# p214_001_001.net
KiCad netlist of a schematic drawn in EAGLE
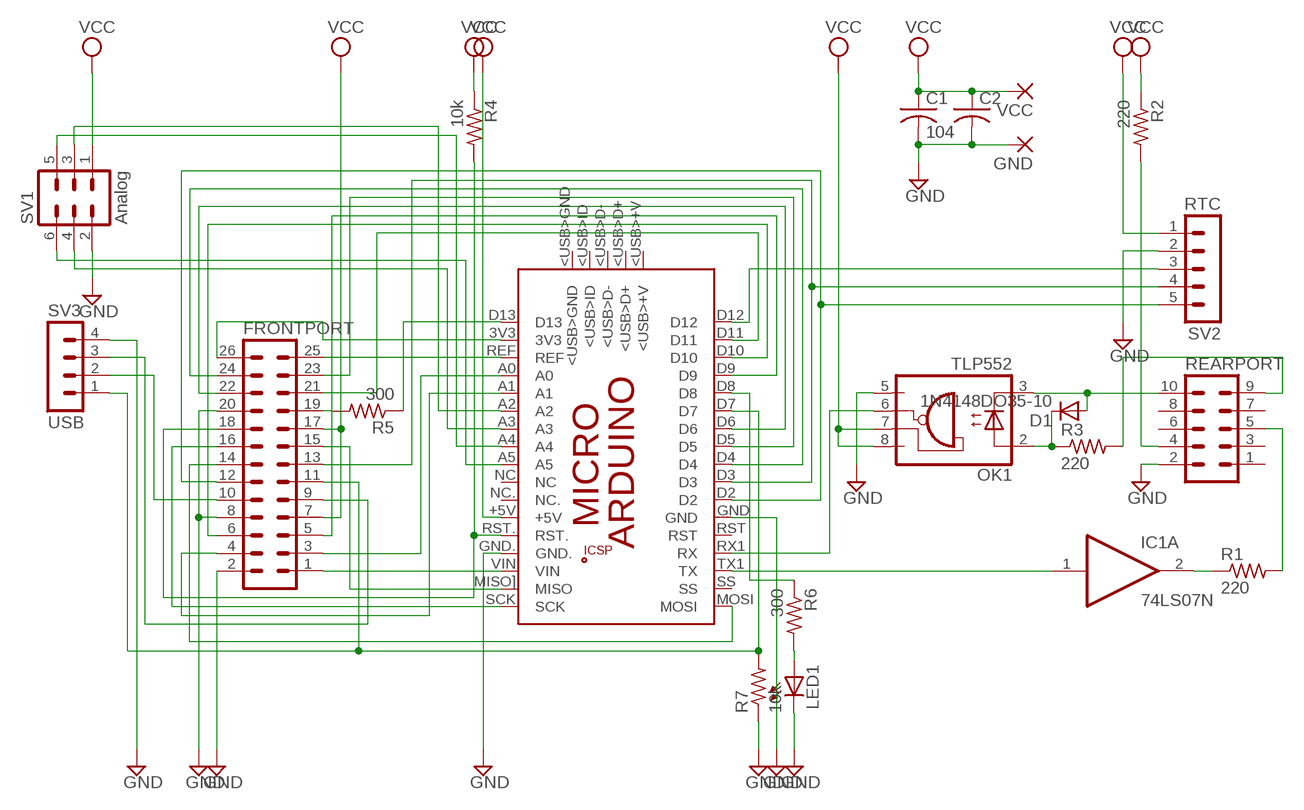
[diagram p0: schematic, sheet 1]

(export (version "E")
  (design (tool "Eeschema 10.0.6"))
  (components
    (comp (ref "C1")
      (value "104")
      (footprint "eagle-import:C025-025X050")
      (libsource (lib "eagle-import") (part "C-US025-025X050"))
    )
    (comp (ref "C2")
      (value "C-US050-075X075")
      (footprint "eagle-import:C050-075X075")
      (libsource (lib "eagle-import") (part "C-US050-075X075"))
    )
    (comp (ref "D1")
      (value "1N4148DO35-10")
      (footprint "eagle-import:DO35-10")
      (libsource (lib "eagle-import") (part "1N4148DO35-10"))
    )
    (comp (ref "FRONTPORT")
      (value "ML26L")
      (footprint "eagle-import:ML26L")
      (libsource (lib "eagle-import") (part "ML26L"))
    )
    (comp (ref "GND")
      (value "1,6/0,9")
      (footprint "eagle-import:1,6_0,9")
      (libsource (lib "eagle-import") (part "1,6/0,9"))
    )
    (comp (ref "IC1")
      (value "74LS07N")
      (footprint "eagle-import:DIL14")
      (libsource (lib "eagle-import") (part "7407NLS"))
    )
    (comp (ref "LED1")
      (value "LED3MM")
      (footprint "eagle-import:LED3MM")
      (libsource (lib "eagle-import") (part "LED3MM"))
    )
    (comp (ref "OK1")
      (value "TLP552")
      (footprint "eagle-import:DIL08")
      (fields (field (name "MPN") "6N137"))
      (libsource (lib "eagle-import") (part "6N137"))
    )
    (comp (ref "PCB1")
      (value "ARDUINO_MICRO")
      (footprint "eagle-import:ARDUINO_MICRO")
      (libsource (lib "eagle-import") (part "ARDUINO_MICRO"))
    )
    (comp (ref "R1")
      (value "220")
      (footprint "eagle-import:0204_7")
      (libsource (lib "eagle-import") (part "R-US_0204/7"))
    )
    (comp (ref "R2")
      (value "220")
      (footprint "eagle-import:0204_7")
      (libsource (lib "eagle-import") (part "R-US_0204/7"))
    )
    (comp (ref "R3")
      (value "220")
      (footprint "eagle-import:0204_7")
      (libsource (lib "eagle-import") (part "R-US_0204/7"))
    )
    (comp (ref "R4")
      (value "10k")
      (footprint "eagle-import:0204_7")
      (libsource (lib "eagle-import") (part "R-US_0204/7"))
    )
    (comp (ref "R5")
      (value "300")
      (footprint "eagle-import:0204_7")
      (libsource (lib "eagle-import") (part "R-US_0204/7"))
    )
    (comp (ref "R6")
      (value "300")
      (footprint "eagle-import:0204_7")
      (libsource (lib "eagle-import") (part "R-US_0204/7"))
    )
    (comp (ref "R7")
      (value "10k")
      (footprint "eagle-import:0204_7")
      (libsource (lib "eagle-import") (part "R-US_0204/7"))
    )
    (comp (ref "REARPORT")
      (value "ML10L")
      (footprint "eagle-import:ML10L")
      (libsource (lib "eagle-import") (part "ML10L"))
    )
    (comp (ref "SV1")
      (value "Analog")
      (footprint "eagle-import:MA03-2")
      (libsource (lib "eagle-import") (part "MA03-2"))
    )
    (comp (ref "SV2")
      (value "RTC")
      (footprint "eagle-import:MA05-1")
      (libsource (lib "eagle-import") (part "MA05-1"))
    )
    (comp (ref "SV3")
      (value "USB")
      (footprint "eagle-import:MA04-1")
      (libsource (lib "eagle-import") (part "MA04-1"))
    )
    (comp (ref "VCC")
      (value "1,6/0,9")
      (footprint "eagle-import:1,6_0,9")
      (libsource (lib "eagle-import") (part "1,6/0,9"))
    )
  )
  (nets
    (net (code "1") (name "GND") (class "Default")
      (node (ref "C1") (pin "2") (pinfunction "2_2") (pintype "passive"))
      (node (ref "C2") (pin "2") (pinfunction "2_2") (pintype "passive"))
      (node (ref "FRONTPORT") (pin "2") (pinfunction "2_2") (pintype "passive"))
      (node (ref "FRONTPORT") (pin "20") (pinfunction "20_20") (pintype "passive"))
      (node (ref "FRONTPORT") (pin "8") (pinfunction "8_8") (pintype "passive"))
      (node (ref "GND") (pin "1") (pinfunction "P_1") (pintype "passive"))
      (node (ref "LED1") (pin "K") (pinfunction "C_K") (pintype "passive"))
      (node (ref "OK1") (pin "5") (pinfunction "GND_5") (pintype "passive"))
      (node (ref "PCB1") (pin "GND") (pinfunction "GND_GND") (pintype "bidirectional"))
      (node (ref "PCB1") (pin "GND.") (pinfunction "GND._GND.") (pintype "bidirectional"))
      (node (ref "R7") (pin "1") (pinfunction "1_1") (pintype "passive"))
      (node (ref "REARPORT") (pin "2") (pinfunction "2_2") (pintype "passive"))
      (node (ref "SV1") (pin "2") (pinfunction "2_2") (pintype "passive"))
      (node (ref "SV2") (pin "2") (pinfunction "2_2") (pintype "passive"))
      (node (ref "SV3") (pin "4") (pinfunction "4_4") (pintype "passive"))
    )
    (net (code "2") (name "Net-(FRONTPORT-Pad1)") (class "Default")
      (node (ref "FRONTPORT") (pin "1") (pinfunction "1_1") (pintype "passive"))
      (node (ref "PCB1") (pin "VIN") (pinfunction "VIN_VIN") (pintype "bidirectional"))
    )
    (net (code "3") (name "Net-(FRONTPORT-Pad3)") (class "Default")
      (node (ref "FRONTPORT") (pin "3") (pinfunction "3_3") (pintype "passive"))
      (node (ref "PCB1") (pin "A0") (pinfunction "A0_A0") (pintype "bidirectional"))
    )
    (net (code "4") (name "Net-(FRONTPORT-Pad4)") (class "Default")
      (node (ref "FRONTPORT") (pin "4") (pinfunction "4_4") (pintype "passive"))
      (node (ref "PCB1") (pin "A1") (pinfunction "A1_A1") (pintype "bidirectional"))
    )
    (net (code "5") (name "Net-(FRONTPORT-Pad5)") (class "Default")
      (node (ref "FRONTPORT") (pin "5") (pinfunction "5_5") (pintype "passive"))
      (node (ref "PCB1") (pin "D9") (pinfunction "D9_D9") (pintype "bidirectional"))
    )
    (net (code "6") (name "Net-(FRONTPORT-Pad6)") (class "Default")
      (node (ref "FRONTPORT") (pin "6") (pinfunction "6_6") (pintype "passive"))
      (node (ref "PCB1") (pin "D10") (pinfunction "D10_D10") (pintype "bidirectional"))
    )
    (net (code "7") (name "Net-(FRONTPORT-Pad9)") (class "Default")
      (node (ref "FRONTPORT") (pin "9") (pinfunction "9_9") (pintype "passive"))
      (node (ref "SV3") (pin "3") (pinfunction "3_3") (pintype "passive"))
    )
    (net (code "8") (name "Net-(FRONTPORT-Pad10)") (class "Default")
      (node (ref "FRONTPORT") (pin "10") (pinfunction "10_10") (pintype "passive"))
      (node (ref "SV3") (pin "2") (pinfunction "2_2") (pintype "passive"))
    )
    (net (code "9") (name "Net-(FRONTPORT-Pad11)") (class "Default")
      (node (ref "FRONTPORT") (pin "11") (pinfunction "11_11") (pintype "passive"))
      (node (ref "PCB1") (pin "D7") (pinfunction "D7_D7") (pintype "bidirectional"))
      (node (ref "R7") (pin "2") (pinfunction "2_2") (pintype "passive"))
      (node (ref "SV3") (pin "1") (pinfunction "1_1") (pintype "passive"))
    )
    (net (code "10") (name "Net-(FRONTPORT-Pad12)") (class "Default")
      (node (ref "FRONTPORT") (pin "12") (pinfunction "12_12") (pintype "passive"))
      (node (ref "PCB1") (pin "D2") (pinfunction "D2_D2") (pintype "bidirectional"))
      (node (ref "SV2") (pin "5") (pinfunction "5_5") (pintype "passive"))
    )
    (net (code "11") (name "Net-(FRONTPORT-Pad13)") (class "Default")
      (node (ref "FRONTPORT") (pin "13") (pinfunction "13_13") (pintype "passive"))
      (node (ref "PCB1") (pin "D3") (pinfunction "D3_D3") (pintype "bidirectional"))
      (node (ref "SV2") (pin "4") (pinfunction "4_4") (pintype "passive"))
    )
    (net (code "12") (name "Net-(FRONTPORT-Pad14)") (class "Default")
      (node (ref "FRONTPORT") (pin "14") (pinfunction "14_14") (pintype "passive"))
      (node (ref "PCB1") (pin "MOSI") (pinfunction "MOSI_MOSI") (pintype "bidirectional"))
    )
    (net (code "13") (name "Net-(FRONTPORT-Pad16)") (class "Default")
      (node (ref "FRONTPORT") (pin "16") (pinfunction "16_16") (pintype "passive"))
      (node (ref "PCB1") (pin "SCK") (pinfunction "SCK_SCK") (pintype "bidirectional"))
    )
    (net (code "14") (name "Net-(FRONTPORT-Pad18)") (class "Default")
      (node (ref "FRONTPORT") (pin "18") (pinfunction "18_18") (pintype "passive"))
      (node (ref "PCB1") (pin "RST.") (pinfunction "RST._RST.") (pintype "bidirectional"))
      (node (ref "R4") (pin "2") (pinfunction "2_2") (pintype "passive"))
    )
    (net (code "15") (name "Net-(FRONTPORT-Pad19)") (class "Default")
      (node (ref "FRONTPORT") (pin "19") (pinfunction "19_19") (pintype "passive"))
      (node (ref "R5") (pin "2") (pinfunction "2_2") (pintype "passive"))
    )
    (net (code "16") (name "Net-(FRONTPORT-Pad21)") (class "Default")
      (node (ref "FRONTPORT") (pin "21") (pinfunction "21_21") (pintype "passive"))
      (node (ref "PCB1") (pin "D11") (pinfunction "D11_D11") (pintype "bidirectional"))
    )
    (net (code "17") (name "Net-(FRONTPORT-Pad22)") (class "Default")
      (node (ref "FRONTPORT") (pin "22") (pinfunction "22_22") (pintype "passive"))
      (node (ref "PCB1") (pin "D6") (pinfunction "D6_D6") (pintype "bidirectional"))
    )
    (net (code "18") (name "Net-(FRONTPORT-Pad23)") (class "Default")
      (node (ref "FRONTPORT") (pin "23") (pinfunction "23_23") (pintype "passive"))
      (node (ref "PCB1") (pin "D5") (pinfunction "D5_D5") (pintype "bidirectional"))
    )
    (net (code "19") (name "Net-(FRONTPORT-Pad24)") (class "Default")
      (node (ref "FRONTPORT") (pin "24") (pinfunction "24_24") (pintype "passive"))
      (node (ref "PCB1") (pin "D4") (pinfunction "D4_D4") (pintype "bidirectional"))
    )
    (net (code "20") (name "Net-(FRONTPORT-Pad25)") (class "Default")
      (node (ref "FRONTPORT") (pin "25") (pinfunction "25_25") (pintype "passive"))
      (node (ref "PCB1") (pin "REF") (pinfunction "REF_REF") (pintype "bidirectional"))
    )
    (net (code "21") (name "Net-(FRONTPORT-Pad26)") (class "Default")
      (node (ref "FRONTPORT") (pin "26") (pinfunction "26_26") (pintype "passive"))
      (node (ref "PCB1") (pin "3V3") (pinfunction "3V3_3V3") (pintype "bidirectional"))
    )
    (net (code "22") (name "Net-(IC1A-I)") (class "Default")
      (node (ref "IC1") (pin "1") (pinfunction "I_1") (pintype "input"))
      (node (ref "PCB1") (pin "TX1") (pinfunction "TX_TX1") (pintype "bidirectional"))
    )
    (net (code "23") (name "Net-(IC1A-O)") (class "Default")
      (node (ref "IC1") (pin "2") (pinfunction "O_2") (pintype "open_collector"))
      (node (ref "R1") (pin "1") (pinfunction "1_1") (pintype "passive"))
    )
    (net (code "24") (name "Net-(LED1-PadA)") (class "Default")
      (node (ref "LED1") (pin "A") (pinfunction "A_A") (pintype "passive"))
      (node (ref "R6") (pin "2") (pinfunction "2_2") (pintype "passive"))
    )
    (net (code "25") (name "Net-(OK1-A)") (class "Default")
      (node (ref "D1") (pin "C") (pinfunction "C_C") (pintype "passive"))
      (node (ref "OK1") (pin "2") (pinfunction "A_2") (pintype "passive"))
      (node (ref "R3") (pin "1") (pinfunction "1_1") (pintype "passive"))
    )
    (net (code "26") (name "Net-(OK1-C)") (class "Default")
      (node (ref "D1") (pin "A") (pinfunction "A_A") (pintype "passive"))
      (node (ref "OK1") (pin "3") (pinfunction "C_3") (pintype "passive"))
      (node (ref "REARPORT") (pin "10") (pinfunction "10_10") (pintype "passive"))
    )
    (net (code "27") (name "Net-(OK1-VO)") (class "Default")
      (node (ref "OK1") (pin "6") (pinfunction "VO_6") (pintype "passive"))
      (node (ref "PCB1") (pin "RX1") (pinfunction "RX_RX1") (pintype "bidirectional"))
    )
    (net (code "28") (name "Net-(PCB1-MISO)") (class "Default")
      (node (ref "FRONTPORT") (pin "15") (pinfunction "15_15") (pintype "passive"))
      (node (ref "PCB1") (pin "MISO]") (pinfunction "MISO_MISO]") (pintype "bidirectional"))
    )
    (net (code "29") (name "Net-(PCB1-PadA2)") (class "Default")
      (node (ref "PCB1") (pin "A2") (pinfunction "A2_A2") (pintype "bidirectional"))
      (node (ref "SV1") (pin "3") (pinfunction "3_3") (pintype "passive"))
    )
    (net (code "30") (name "Net-(PCB1-PadA3)") (class "Default")
      (node (ref "PCB1") (pin "A3") (pinfunction "A3_A3") (pintype "bidirectional"))
      (node (ref "SV1") (pin "4") (pinfunction "4_4") (pintype "passive"))
    )
    (net (code "31") (name "Net-(PCB1-PadA4)") (class "Default")
      (node (ref "PCB1") (pin "A4") (pinfunction "A4_A4") (pintype "bidirectional"))
      (node (ref "SV1") (pin "5") (pinfunction "5_5") (pintype "passive"))
    )
    (net (code "32") (name "Net-(PCB1-PadA5)") (class "Default")
      (node (ref "PCB1") (pin "A5") (pinfunction "A5_A5") (pintype "bidirectional"))
      (node (ref "SV1") (pin "6") (pinfunction "6_6") (pintype "passive"))
    )
    (net (code "33") (name "Net-(PCB1-PadD8)") (class "Default")
      (node (ref "PCB1") (pin "D8") (pinfunction "D8_D8") (pintype "bidirectional"))
      (node (ref "R6") (pin "1") (pinfunction "1_1") (pintype "passive"))
    )
    (net (code "34") (name "Net-(PCB1-PadD12)") (class "Default")
      (node (ref "PCB1") (pin "D12") (pinfunction "D12_D12") (pintype "bidirectional"))
      (node (ref "SV2") (pin "3") (pinfunction "3_3") (pintype "passive"))
    )
    (net (code "35") (name "Net-(PCB1-PadD13)") (class "Default")
      (node (ref "PCB1") (pin "D13") (pinfunction "D13_D13") (pintype "bidirectional"))
      (node (ref "R5") (pin "1") (pinfunction "1_1") (pintype "passive"))
    )
    (net (code "36") (name "Net-(R1-Pad2)") (class "Default")
      (node (ref "R1") (pin "2") (pinfunction "2_2") (pintype "passive"))
      (node (ref "REARPORT") (pin "5") (pinfunction "5_5") (pintype "passive"))
    )
    (net (code "37") (name "Net-(R2-Pad2)") (class "Default")
      (node (ref "R2") (pin "2") (pinfunction "2_2") (pintype "passive"))
      (node (ref "REARPORT") (pin "4") (pinfunction "4_4") (pintype "passive"))
    )
    (net (code "38") (name "Net-(R3-Pad2)") (class "Default")
      (node (ref "R3") (pin "2") (pinfunction "2_2") (pintype "passive"))
      (node (ref "REARPORT") (pin "9") (pinfunction "9_9") (pintype "passive"))
    )
    (net (code "39") (name "VCC") (class "Default")
      (node (ref "C1") (pin "1") (pinfunction "1_1") (pintype "passive"))
      (node (ref "C2") (pin "1") (pinfunction "1_1") (pintype "passive"))
      (node (ref "FRONTPORT") (pin "17") (pinfunction "17_17") (pintype "passive"))
      (node (ref "FRONTPORT") (pin "7") (pinfunction "7_7") (pintype "passive"))
      (node (ref "OK1") (pin "7") (pinfunction "VE_7") (pintype "passive"))
      (node (ref "OK1") (pin "8") (pinfunction "VCC_8") (pintype "passive"))
      (node (ref "PCB1") (pin "+5V") (pinfunction "+5V_+5V") (pintype "bidirectional"))
      (node (ref "R2") (pin "1") (pinfunction "1_1") (pintype "passive"))
      (node (ref "R4") (pin "1") (pinfunction "1_1") (pintype "passive"))
      (node (ref "SV1") (pin "1") (pinfunction "1_1") (pintype "passive"))
      (node (ref "SV2") (pin "1") (pinfunction "1_1") (pintype "passive"))
      (node (ref "VCC") (pin "1") (pinfunction "P_1") (pintype "passive"))
    )
    (net (code "40") (name "unconnected-(PCB1-Pad5V)") (class "Default")
      (node (ref "PCB1") (pin "5V") (pinfunction "5V_5V") (pintype "bidirectional"))
    )
    (net (code "41") (name "unconnected-(PCB1-Pad<USB>+V)") (class "Default")
      (node (ref "PCB1") (pin "<USB>+V") (pinfunction "<USB>+V_<USB>+V") (pintype "bidirectional"))
    )
    (net (code "42") (name "unconnected-(PCB1-Pad<USB>D+)") (class "Default")
      (node (ref "PCB1") (pin "<USB>D+") (pinfunction "<USB>D+_<USB>D+") (pintype "bidirectional"))
    )
    (net (code "43") (name "unconnected-(PCB1-Pad<USB>D-)") (class "Default")
      (node (ref "PCB1") (pin "<USB>D-") (pinfunction "<USB>D-_<USB>D-") (pintype "bidirectional"))
    )
    (net (code "44") (name "unconnected-(PCB1-Pad<USB>GND)") (class "Default")
      (node (ref "PCB1") (pin "<USB>GND") (pinfunction "<USB>GND_<USB>GND") (pintype "bidirectional"))
    )
    (net (code "45") (name "unconnected-(PCB1-Pad<USB>ID)") (class "Default")
      (node (ref "PCB1") (pin "<USB>ID") (pinfunction "<USB>ID_<USB>ID") (pintype "bidirectional"))
    )
    (net (code "46") (name "unconnected-(PCB1-PadGND_)") (class "Default")
      (node (ref "PCB1") (pin "GND_") (pinfunction "GND__GND_") (pintype "bidirectional"))
    )
    (net (code "47") (name "unconnected-(PCB1-PadMISO.)") (class "Default")
      (node (ref "PCB1") (pin "MISO.") (pinfunction "MISO._MISO.") (pintype "bidirectional"))
    )
    (net (code "48") (name "unconnected-(PCB1-PadMOSI.)") (class "Default")
      (node (ref "PCB1") (pin "MOSI.") (pinfunction "MOSI._MOSI.") (pintype "bidirectional"))
    )
    (net (code "49") (name "unconnected-(PCB1-PadNC)") (class "Default")
      (node (ref "PCB1") (pin "NC") (pinfunction "NC_NC") (pintype "bidirectional"))
    )
    (net (code "50") (name "unconnected-(PCB1-PadNC.)") (class "Default")
      (node (ref "PCB1") (pin "NC.") (pinfunction "NC._NC.") (pintype "bidirectional"))
    )
    (net (code "51") (name "unconnected-(PCB1-PadRESET..)") (class "Default")
      (node (ref "PCB1") (pin "RESET..") (pinfunction "RESET.._RESET..") (pintype "bidirectional"))
    )
    (net (code "52") (name "unconnected-(PCB1-PadRST)") (class "Default")
      (node (ref "PCB1") (pin "RST") (pinfunction "RST_RST") (pintype "bidirectional"))
    )
    (net (code "53") (name "unconnected-(PCB1-PadSCK.)") (class "Default")
      (node (ref "PCB1") (pin "SCK.") (pinfunction "SCK._SCK.") (pintype "bidirectional"))
    )
    (net (code "54") (name "unconnected-(PCB1-PadSS)") (class "Default")
      (node (ref "PCB1") (pin "SS") (pinfunction "SS_SS") (pintype "bidirectional"))
    )
    (net (code "55") (name "unconnected-(REARPORT-Pad1)") (class "Default")
      (node (ref "REARPORT") (pin "1") (pinfunction "1_1") (pintype "passive"))
    )
    (net (code "56") (name "unconnected-(REARPORT-Pad3)") (class "Default")
      (node (ref "REARPORT") (pin "3") (pinfunction "3_3") (pintype "passive"))
    )
    (net (code "57") (name "unconnected-(REARPORT-Pad6)") (class "Default")
      (node (ref "REARPORT") (pin "6") (pinfunction "6_6") (pintype "passive"))
    )
    (net (code "58") (name "unconnected-(REARPORT-Pad7)") (class "Default")
      (node (ref "REARPORT") (pin "7") (pinfunction "7_7") (pintype "passive"))
    )
    (net (code "59") (name "unconnected-(REARPORT-Pad8)") (class "Default")
      (node (ref "REARPORT") (pin "8") (pinfunction "8_8") (pintype "passive"))
    )
  )
)
